# DE-211024_3.net
KiCad netlist of a schematic drawn in Altium Designer
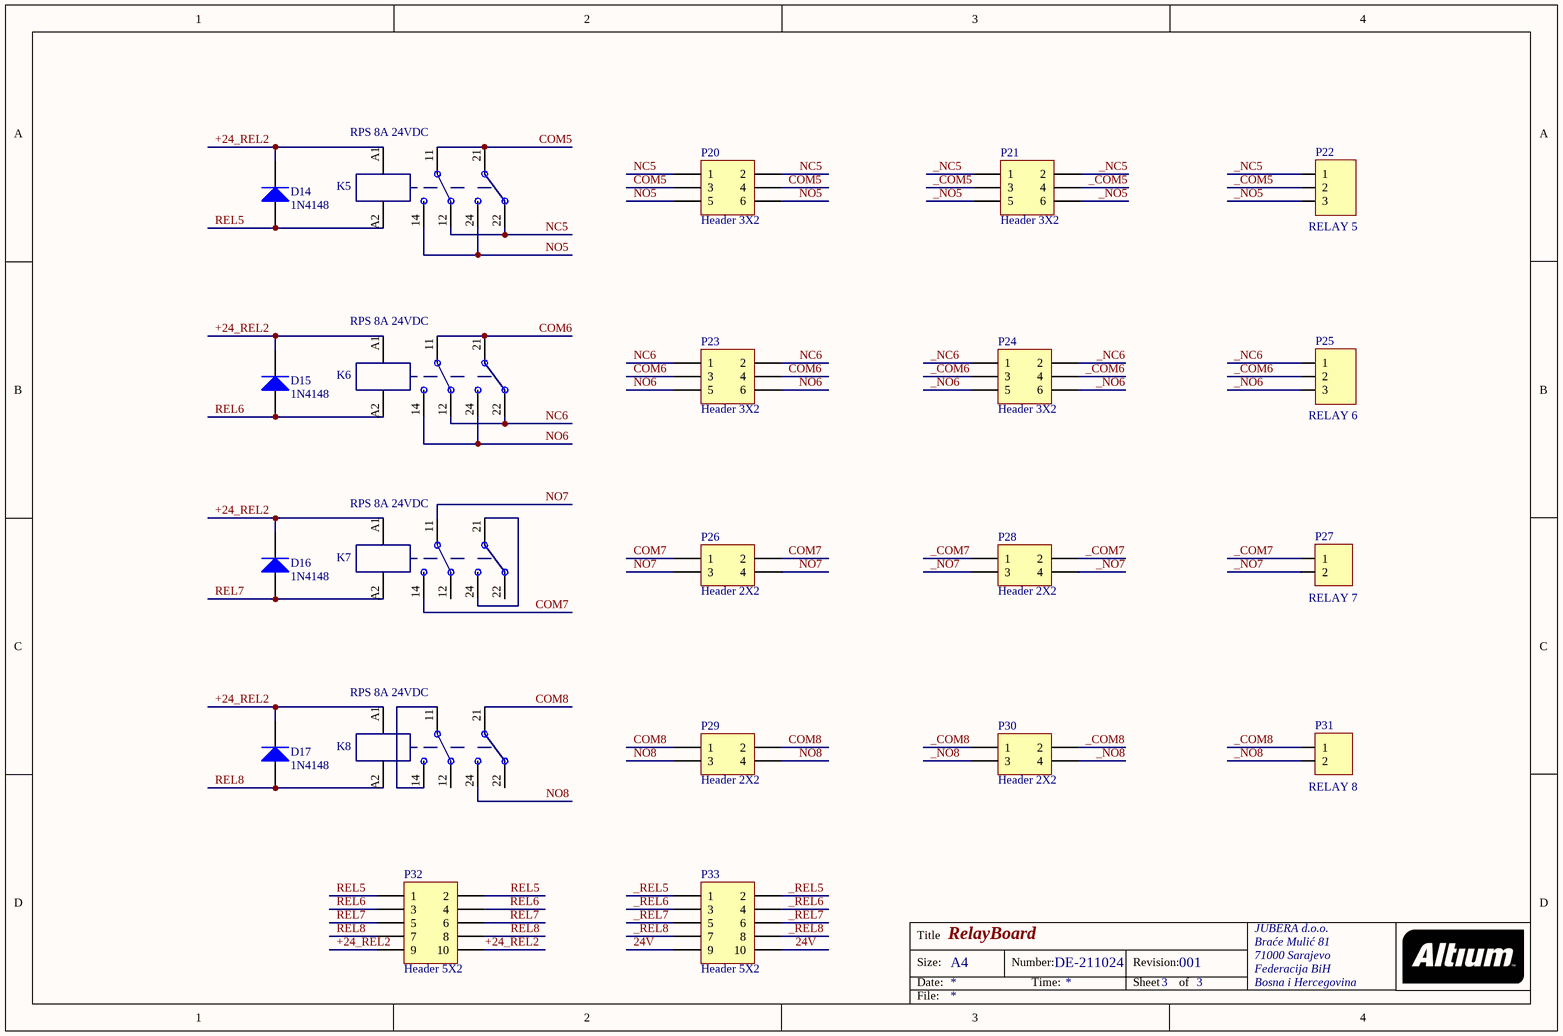
[diagram p0: DE-211024_3.SchDoc]

(export (version "E")
  (design (tool "Eeschema 10.0.6"))
  (components
    (comp (ref "D14")
      (value "1N4148")
      (footprint "SOD323")
      (description "General-purpose Diode")
      (fields (field (name "PUBLISHER") "Altium Limited"))
      (libsource (lib "DE-211024") (part "BAS321"))
    )
    (comp (ref "D15")
      (value "1N4148")
      (footprint "SOD323")
      (description "General-purpose Diode")
      (fields (field (name "PUBLISHER") "Altium Limited"))
      (libsource (lib "DE-211024") (part "BAS321"))
    )
    (comp (ref "D16")
      (value "1N4148")
      (footprint "SOD323")
      (description "General-purpose Diode")
      (fields (field (name "PUBLISHER") "Altium Limited"))
      (libsource (lib "DE-211024") (part "BAS321"))
    )
    (comp (ref "D17")
      (value "1N4148")
      (footprint "SOD323")
      (description "General-purpose Diode")
      (fields (field (name "PUBLISHER") "Altium Limited"))
      (libsource (lib "DE-211024") (part "BAS321"))
    )
    (comp (ref "K5")
      (value "RPS 8A 24VDC")
      (footprint "RPS 2CO 8A 24V")
      (libsource (lib "DE-211024") (part "PCB relay 2CO, 8A, 24VDC, RPS serie 5mm"))
    )
    (comp (ref "K6")
      (value "RPS 8A 24VDC")
      (footprint "RPS 2CO 8A 24V")
      (libsource (lib "DE-211024") (part "PCB relay 2CO, 8A, 24VDC, RPS serie 5mm"))
    )
    (comp (ref "K7")
      (value "RPS 8A 24VDC")
      (footprint "RPS 2CO 8A 24V")
      (libsource (lib "DE-211024") (part "PCB relay 2CO, 8A, 24VDC, RPS serie 5mm"))
    )
    (comp (ref "K8")
      (value "RPS 8A 24VDC")
      (footprint "RPS 2CO 8A 24V")
      (libsource (lib "DE-211024") (part "PCB relay 2CO, 8A, 24VDC, RPS serie 5mm"))
    )
    (comp (ref "P20")
      (value "Header 3X2")
      (footprint "HDR2X3")
      (description "Header, 3-Pin, Dual row")
      (fields (field (name "PUBLISHER") "Altium Limited"))
      (libsource (lib "Miscellaneous Connectors") (part "Header 3X2"))
    )
    (comp (ref "P21")
      (value "Header 3X2")
      (footprint "HDR2X3")
      (description "Header, 3-Pin, Dual row")
      (fields (field (name "PUBLISHER") "Altium Limited"))
      (libsource (lib "Miscellaneous Connectors") (part "Header 3X2"))
    )
    (comp (ref "P22")
      (value "RELAY 5")
      (footprint "TERMINAL BLOK 3")
      (description "3 pinski terminal blok konektor")
      (libsource (lib "DE-211024") (part "TERMINAL BLOK 3"))
    )
    (comp (ref "P23")
      (value "Header 3X2")
      (footprint "HDR2X3")
      (description "Header, 3-Pin, Dual row")
      (fields (field (name "PUBLISHER") "Altium Limited"))
      (libsource (lib "Miscellaneous Connectors") (part "Header 3X2"))
    )
    (comp (ref "P24")
      (value "Header 3X2")
      (footprint "HDR2X3")
      (description "Header, 3-Pin, Dual row")
      (fields (field (name "PUBLISHER") "Altium Limited"))
      (libsource (lib "Miscellaneous Connectors") (part "Header 3X2"))
    )
    (comp (ref "P25")
      (value "RELAY 6")
      (footprint "TERMINAL BLOK 3")
      (description "3 pinski terminal blok konektor")
      (libsource (lib "DE-211024") (part "TERMINAL BLOK 3"))
    )
    (comp (ref "P26")
      (value "Header 2X2")
      (footprint "HDR2X2")
      (description "Header, 2-Pin, Dual row")
      (fields (field (name "PUBLISHER") "Altium Limited"))
      (libsource (lib "Miscellaneous Connectors") (part "Header 2X2"))
    )
    (comp (ref "P27")
      (value "RELAY 7")
      (footprint "TERMINAL BLOK 2")
      (description "Terminal blok konektor 3,5 mm")
      (libsource (lib "DE-211024") (part "TERMINAL BLOK 2"))
    )
    (comp (ref "P28")
      (value "Header 2X2")
      (footprint "HDR2X2")
      (description "Header, 2-Pin, Dual row")
      (fields (field (name "PUBLISHER") "Altium Limited"))
      (libsource (lib "Miscellaneous Connectors") (part "Header 2X2"))
    )
    (comp (ref "P29")
      (value "Header 2X2")
      (footprint "HDR2X2")
      (description "Header, 2-Pin, Dual row")
      (fields (field (name "PUBLISHER") "Altium Limited"))
      (libsource (lib "Miscellaneous Connectors") (part "Header 2X2"))
    )
    (comp (ref "P30")
      (value "Header 2X2")
      (footprint "HDR2X2")
      (description "Header, 2-Pin, Dual row")
      (fields (field (name "PUBLISHER") "Altium Limited"))
      (libsource (lib "Miscellaneous Connectors") (part "Header 2X2"))
    )
    (comp (ref "P31")
      (value "RELAY 8")
      (footprint "TERMINAL BLOK 2")
      (description "Terminal blok konektor 3,5 mm")
      (libsource (lib "DE-211024") (part "TERMINAL BLOK 2"))
    )
    (comp (ref "P32")
      (value "Header 5X2")
      (footprint "HDR2X5")
      (description "Header, 5-Pin, Dual row")
      (fields (field (name "PUBLISHER") "Altium Limited"))
      (libsource (lib "Miscellaneous Connectors") (part "Header 5X2"))
    )
    (comp (ref "P33")
      (value "Header 5X2")
      (footprint "HDR2X5")
      (description "Header, 5-Pin, Dual row")
      (fields (field (name "PUBLISHER") "Altium Limited"))
      (libsource (lib "Miscellaneous Connectors") (part "Header 5X2"))
    )
  )
  (nets
    (net (code "1") (name "/+24_REL2") (class "Default")
      (node (ref "D14") (pin "1") (pinfunction "K_1") (pintype "passive"))
      (node (ref "D15") (pin "1") (pinfunction "K_1") (pintype "passive"))
      (node (ref "D16") (pin "1") (pinfunction "K_1") (pintype "passive"))
      (node (ref "D17") (pin "1") (pinfunction "K_1") (pintype "passive"))
      (node (ref "K5") (pin "A1") (pinfunction "1_A1") (pintype "passive"))
      (node (ref "K6") (pin "A1") (pinfunction "1_A1") (pintype "passive"))
      (node (ref "K7") (pin "A1") (pinfunction "1_A1") (pintype "passive"))
      (node (ref "K8") (pin "A1") (pinfunction "1_A1") (pintype "passive"))
      (node (ref "P32") (pin "10") (pinfunction "10_10") (pintype "passive"))
      (node (ref "P32") (pin "9") (pinfunction "9_9") (pintype "passive"))
    )
    (net (code "2") (name "/24V") (class "Default")
      (node (ref "P33") (pin "10") (pinfunction "10_10") (pintype "passive"))
      (node (ref "P33") (pin "9") (pinfunction "9_9") (pintype "passive"))
    )
    (net (code "3") (name "/COM5") (class "Default")
      (node (ref "K5") (pin "11") (pinfunction "3_11") (pintype "passive"))
      (node (ref "K5") (pin "21") (pinfunction "3_21") (pintype "passive"))
      (node (ref "P20") (pin "3") (pinfunction "3_3") (pintype "passive"))
      (node (ref "P20") (pin "4") (pinfunction "4_4") (pintype "passive"))
    )
    (net (code "4") (name "/COM6") (class "Default")
      (node (ref "K6") (pin "11") (pinfunction "3_11") (pintype "passive"))
      (node (ref "K6") (pin "21") (pinfunction "3_21") (pintype "passive"))
      (node (ref "P23") (pin "3") (pinfunction "3_3") (pintype "passive"))
      (node (ref "P23") (pin "4") (pinfunction "4_4") (pintype "passive"))
    )
    (net (code "5") (name "/COM7") (class "Default")
      (node (ref "K7") (pin "14") (pinfunction "4_14") (pintype "passive"))
      (node (ref "P26") (pin "1") (pinfunction "1_1") (pintype "passive"))
      (node (ref "P26") (pin "2") (pinfunction "2_2") (pintype "passive"))
    )
    (net (code "6") (name "/COM8") (class "Default")
      (node (ref "K8") (pin "21") (pinfunction "3_21") (pintype "passive"))
      (node (ref "P29") (pin "1") (pinfunction "1_1") (pintype "passive"))
      (node (ref "P29") (pin "2") (pinfunction "2_2") (pintype "passive"))
    )
    (net (code "7") (name "/NC5") (class "Default")
      (node (ref "K5") (pin "12") (pinfunction "5_12") (pintype "passive"))
      (node (ref "K5") (pin "22") (pinfunction "5_22") (pintype "passive"))
      (node (ref "P20") (pin "1") (pinfunction "1_1") (pintype "passive"))
      (node (ref "P20") (pin "2") (pinfunction "2_2") (pintype "passive"))
    )
    (net (code "8") (name "/NC6") (class "Default")
      (node (ref "K6") (pin "12") (pinfunction "5_12") (pintype "passive"))
      (node (ref "K6") (pin "22") (pinfunction "5_22") (pintype "passive"))
      (node (ref "P23") (pin "1") (pinfunction "1_1") (pintype "passive"))
      (node (ref "P23") (pin "2") (pinfunction "2_2") (pintype "passive"))
    )
    (net (code "9") (name "/NO5") (class "Default")
      (node (ref "K5") (pin "14") (pinfunction "4_14") (pintype "passive"))
      (node (ref "K5") (pin "24") (pinfunction "4_24") (pintype "passive"))
      (node (ref "P20") (pin "5") (pinfunction "5_5") (pintype "passive"))
      (node (ref "P20") (pin "6") (pinfunction "6_6") (pintype "passive"))
    )
    (net (code "10") (name "/NO6") (class "Default")
      (node (ref "K6") (pin "14") (pinfunction "4_14") (pintype "passive"))
      (node (ref "K6") (pin "24") (pinfunction "4_24") (pintype "passive"))
      (node (ref "P23") (pin "5") (pinfunction "5_5") (pintype "passive"))
      (node (ref "P23") (pin "6") (pinfunction "6_6") (pintype "passive"))
    )
    (net (code "11") (name "/NO7") (class "Default")
      (node (ref "K7") (pin "11") (pinfunction "3_11") (pintype "passive"))
      (node (ref "P26") (pin "3") (pinfunction "3_3") (pintype "passive"))
      (node (ref "P26") (pin "4") (pinfunction "4_4") (pintype "passive"))
    )
    (net (code "12") (name "/NO8") (class "Default")
      (node (ref "K8") (pin "24") (pinfunction "4_24") (pintype "passive"))
      (node (ref "P29") (pin "3") (pinfunction "3_3") (pintype "passive"))
      (node (ref "P29") (pin "4") (pinfunction "4_4") (pintype "passive"))
    )
    (net (code "13") (name "/REL5") (class "Default")
      (node (ref "D14") (pin "2") (pinfunction "A_2") (pintype "passive"))
      (node (ref "K5") (pin "A2") (pinfunction "2_A2") (pintype "passive"))
      (node (ref "P32") (pin "1") (pinfunction "1_1") (pintype "passive"))
      (node (ref "P32") (pin "2") (pinfunction "2_2") (pintype "passive"))
    )
    (net (code "14") (name "/REL6") (class "Default")
      (node (ref "D15") (pin "2") (pinfunction "A_2") (pintype "passive"))
      (node (ref "K6") (pin "A2") (pinfunction "2_A2") (pintype "passive"))
      (node (ref "P32") (pin "3") (pinfunction "3_3") (pintype "passive"))
      (node (ref "P32") (pin "4") (pinfunction "4_4") (pintype "passive"))
    )
    (net (code "15") (name "/REL7") (class "Default")
      (node (ref "D16") (pin "2") (pinfunction "A_2") (pintype "passive"))
      (node (ref "K7") (pin "A2") (pinfunction "2_A2") (pintype "passive"))
      (node (ref "P32") (pin "5") (pinfunction "5_5") (pintype "passive"))
      (node (ref "P32") (pin "6") (pinfunction "6_6") (pintype "passive"))
    )
    (net (code "16") (name "/REL8") (class "Default")
      (node (ref "D17") (pin "2") (pinfunction "A_2") (pintype "passive"))
      (node (ref "K8") (pin "A2") (pinfunction "2_A2") (pintype "passive"))
      (node (ref "P32") (pin "7") (pinfunction "7_7") (pintype "passive"))
      (node (ref "P32") (pin "8") (pinfunction "8_8") (pintype "passive"))
    )
    (net (code "17") (name "/_COM5") (class "Default")
      (node (ref "P21") (pin "3") (pinfunction "3_3") (pintype "passive"))
      (node (ref "P21") (pin "4") (pinfunction "4_4") (pintype "passive"))
      (node (ref "P22") (pin "2") (pinfunction "2_2") (pintype "passive"))
    )
    (net (code "18") (name "/_COM6") (class "Default")
      (node (ref "P24") (pin "3") (pinfunction "3_3") (pintype "passive"))
      (node (ref "P24") (pin "4") (pinfunction "4_4") (pintype "passive"))
      (node (ref "P25") (pin "2") (pinfunction "2_2") (pintype "passive"))
    )
    (net (code "19") (name "/_COM7") (class "Default")
      (node (ref "P27") (pin "1") (pinfunction "1_1") (pintype "passive"))
      (node (ref "P28") (pin "1") (pinfunction "1_1") (pintype "passive"))
      (node (ref "P28") (pin "2") (pinfunction "2_2") (pintype "passive"))
    )
    (net (code "20") (name "/_COM8") (class "Default")
      (node (ref "P30") (pin "1") (pinfunction "1_1") (pintype "passive"))
      (node (ref "P30") (pin "2") (pinfunction "2_2") (pintype "passive"))
      (node (ref "P31") (pin "1") (pinfunction "1_1") (pintype "passive"))
    )
    (net (code "21") (name "/_NC5") (class "Default")
      (node (ref "P21") (pin "1") (pinfunction "1_1") (pintype "passive"))
      (node (ref "P21") (pin "2") (pinfunction "2_2") (pintype "passive"))
      (node (ref "P22") (pin "1") (pinfunction "1_1") (pintype "passive"))
    )
    (net (code "22") (name "/_NC6") (class "Default")
      (node (ref "P24") (pin "1") (pinfunction "1_1") (pintype "passive"))
      (node (ref "P24") (pin "2") (pinfunction "2_2") (pintype "passive"))
      (node (ref "P25") (pin "1") (pinfunction "1_1") (pintype "passive"))
    )
    (net (code "23") (name "/_NO5") (class "Default")
      (node (ref "P21") (pin "5") (pinfunction "5_5") (pintype "passive"))
      (node (ref "P21") (pin "6") (pinfunction "6_6") (pintype "passive"))
      (node (ref "P22") (pin "3") (pinfunction "3_3") (pintype "passive"))
    )
    (net (code "24") (name "/_NO6") (class "Default")
      (node (ref "P24") (pin "5") (pinfunction "5_5") (pintype "passive"))
      (node (ref "P24") (pin "6") (pinfunction "6_6") (pintype "passive"))
      (node (ref "P25") (pin "3") (pinfunction "3_3") (pintype "passive"))
    )
    (net (code "25") (name "/_NO7") (class "Default")
      (node (ref "P27") (pin "2") (pinfunction "2_2") (pintype "passive"))
      (node (ref "P28") (pin "3") (pinfunction "3_3") (pintype "passive"))
      (node (ref "P28") (pin "4") (pinfunction "4_4") (pintype "passive"))
    )
    (net (code "26") (name "/_NO8") (class "Default")
      (node (ref "P30") (pin "3") (pinfunction "3_3") (pintype "passive"))
      (node (ref "P30") (pin "4") (pinfunction "4_4") (pintype "passive"))
      (node (ref "P31") (pin "2") (pinfunction "2_2") (pintype "passive"))
    )
    (net (code "27") (name "/_REL5") (class "Default")
      (node (ref "P33") (pin "1") (pinfunction "1_1") (pintype "passive"))
      (node (ref "P33") (pin "2") (pinfunction "2_2") (pintype "passive"))
    )
    (net (code "28") (name "/_REL6") (class "Default")
      (node (ref "P33") (pin "3") (pinfunction "3_3") (pintype "passive"))
      (node (ref "P33") (pin "4") (pinfunction "4_4") (pintype "passive"))
    )
    (net (code "29") (name "/_REL7") (class "Default")
      (node (ref "P33") (pin "5") (pinfunction "5_5") (pintype "passive"))
      (node (ref "P33") (pin "6") (pinfunction "6_6") (pintype "passive"))
    )
    (net (code "30") (name "/_REL8") (class "Default")
      (node (ref "P33") (pin "7") (pinfunction "7_7") (pintype "passive"))
      (node (ref "P33") (pin "8") (pinfunction "8_8") (pintype "passive"))
    )
    (net (code "31") (name "Net-(K7-3-Pad21)") (class "Default")
      (node (ref "K7") (pin "21") (pinfunction "3_21") (pintype "passive"))
      (node (ref "K7") (pin "24") (pinfunction "4_24") (pintype "passive"))
    )
    (net (code "32") (name "Net-(K8-3-Pad11)") (class "Default")
      (node (ref "K8") (pin "11") (pinfunction "3_11") (pintype "passive"))
      (node (ref "K8") (pin "14") (pinfunction "4_14") (pintype "passive"))
    )
    (net (code "33") (name "unconnected-(K7-5-Pad12)") (class "Default")
      (node (ref "K7") (pin "12") (pinfunction "5_12") (pintype "passive"))
    )
    (net (code "34") (name "unconnected-(K7-5-Pad22)") (class "Default")
      (node (ref "K7") (pin "22") (pinfunction "5_22") (pintype "passive"))
    )
    (net (code "35") (name "unconnected-(K8-5-Pad12)") (class "Default")
      (node (ref "K8") (pin "12") (pinfunction "5_12") (pintype "passive"))
    )
    (net (code "36") (name "unconnected-(K8-5-Pad22)") (class "Default")
      (node (ref "K8") (pin "22") (pinfunction "5_22") (pintype "passive"))
    )
  )
)
